# MySimpleRFMdongle_rev2.net
KiCad netlist of a schematic drawn in EAGLE
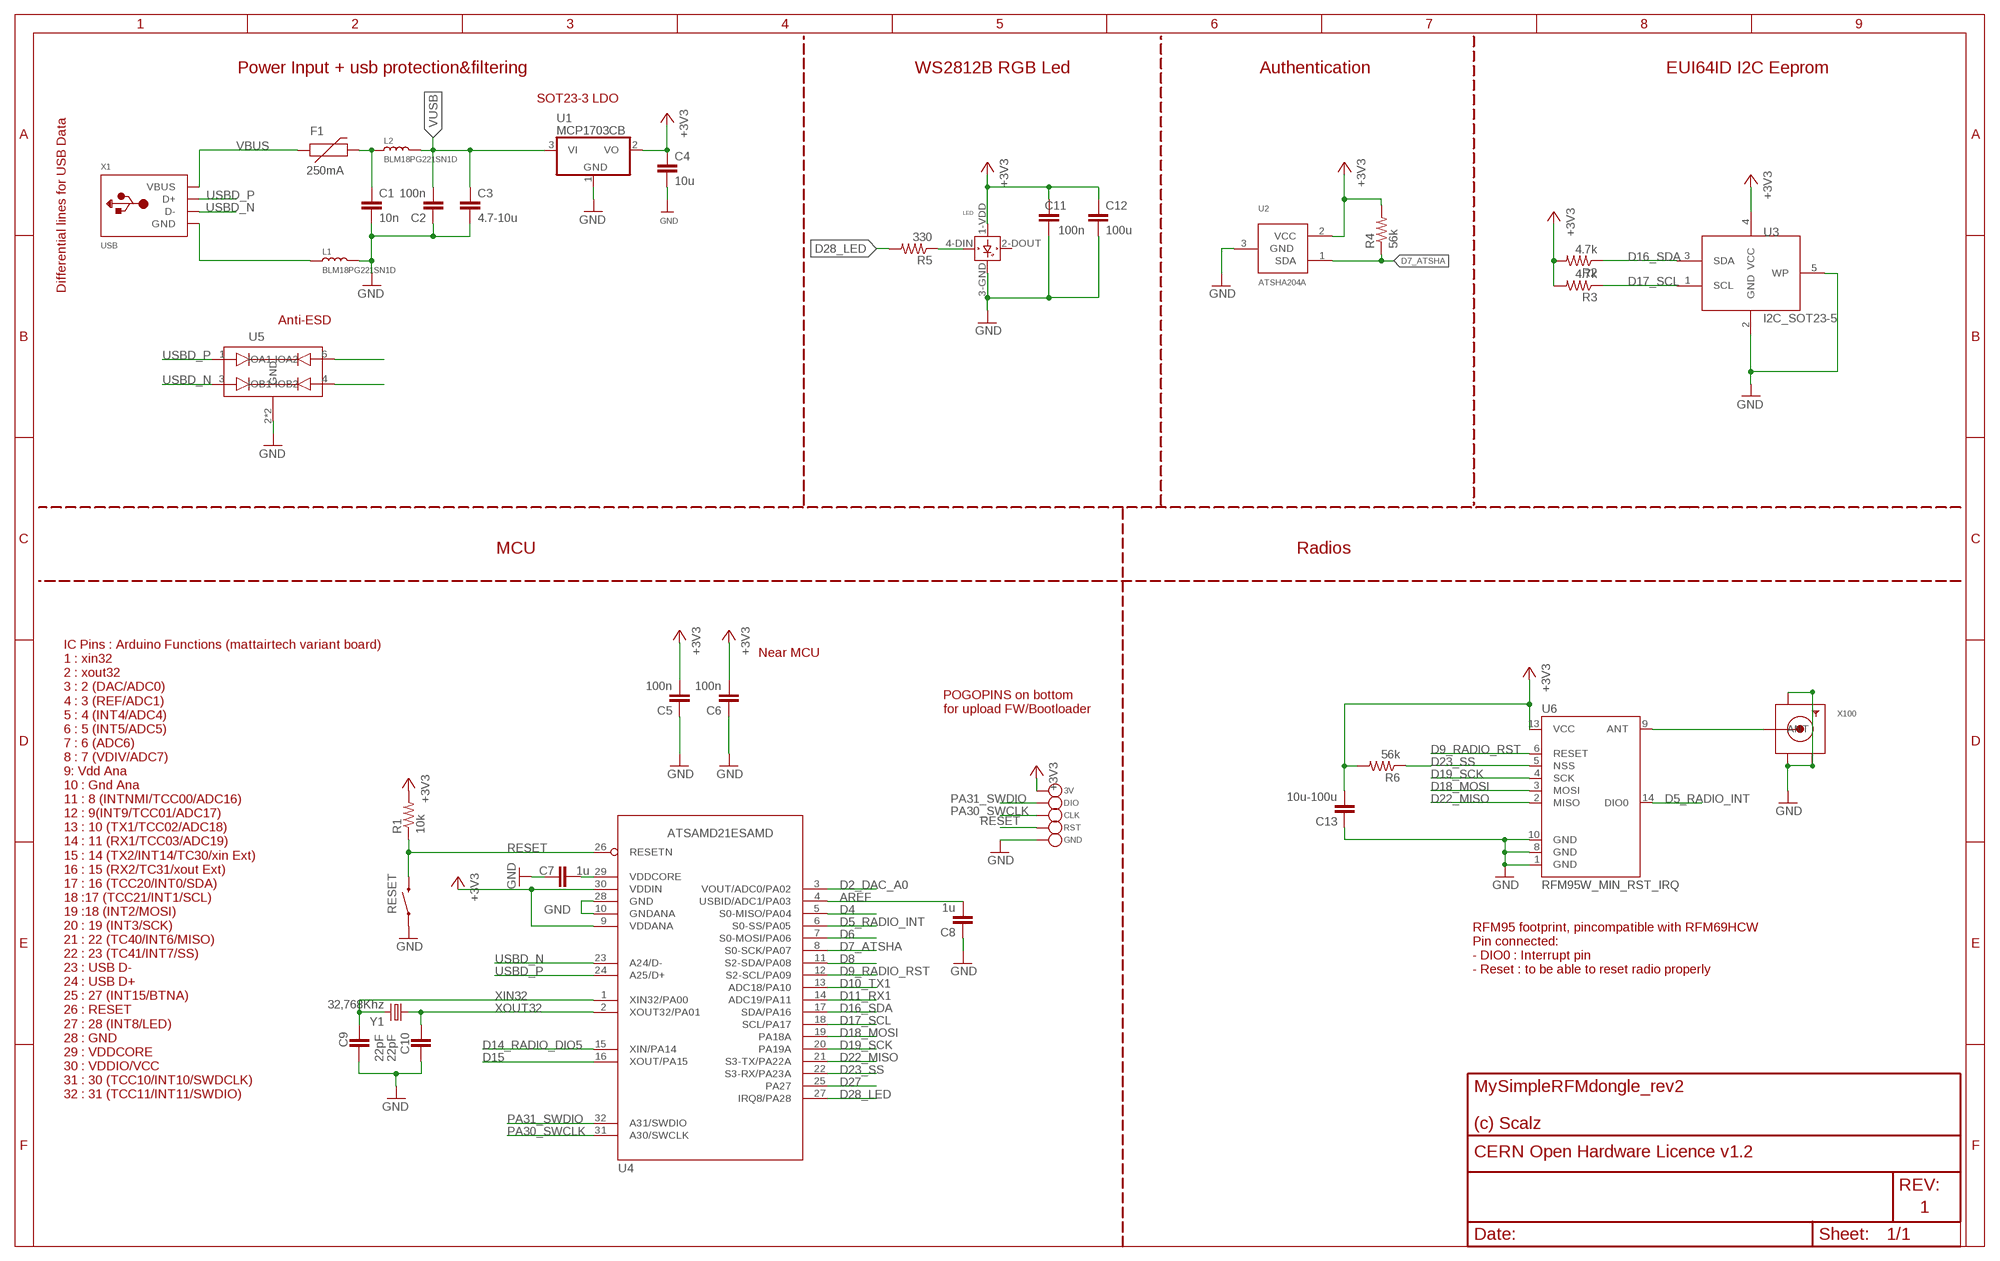
[diagram p0: schematic, sheet 1]

(export (version "E")
  (design (tool "Eeschema 10.0.6"))
  (components
    (comp (ref "3V")
      (value "TESTPOINTROUND1.5MM")
      (footprint "eagle-import:TESTPOINT_ROUND_1.5MM")
      (libsource (lib "eagle-import") (part "TESTPOINTROUND1.5MM"))
    )
    (comp (ref "C1")
      (value "10n")
      (footprint "eagle-import:0603-CAP")
      (libsource (lib "eagle-import") (part "CAP0603-CAP"))
    )
    (comp (ref "C2")
      (value "100n")
      (footprint "eagle-import:0603-CAP")
      (libsource (lib "eagle-import") (part "CAP0603-CAP"))
    )
    (comp (ref "C3")
      (value "4.7-10u")
      (footprint "eagle-import:0805-CAP")
      (libsource (lib "eagle-import") (part "CAP0805-CAP"))
    )
    (comp (ref "C4")
      (value "10u")
      (footprint "eagle-import:0805-CAP")
      (libsource (lib "eagle-import") (part "CAP0805-CAP"))
    )
    (comp (ref "C5")
      (value "100n")
      (footprint "eagle-import:0805-CAP")
      (libsource (lib "eagle-import") (part "CAP0805-CAP"))
    )
    (comp (ref "C6")
      (value "100n")
      (footprint "eagle-import:0603-CAP")
      (libsource (lib "eagle-import") (part "CAP0603-CAP"))
    )
    (comp (ref "C7")
      (value "1u")
      (footprint "eagle-import:0805-CAP")
      (libsource (lib "eagle-import") (part "CAP0805-CAP"))
    )
    (comp (ref "C8")
      (value "1u")
      (footprint "eagle-import:0603-CAP")
      (libsource (lib "eagle-import") (part "CAP0603-CAP"))
    )
    (comp (ref "C9")
      (value "22pF")
      (footprint "eagle-import:0603-CAP")
      (libsource (lib "eagle-import") (part "CAP0603-CAP"))
    )
    (comp (ref "C10")
      (value "22pF")
      (footprint "eagle-import:0603-CAP")
      (libsource (lib "eagle-import") (part "CAP0603-CAP"))
    )
    (comp (ref "C11")
      (value "100n")
      (footprint "eagle-import:0603-CAP")
      (libsource (lib "eagle-import") (part "CAP0603-CAP"))
    )
    (comp (ref "C12")
      (value "100u")
      (footprint "eagle-import:0805-CAP")
      (libsource (lib "eagle-import") (part "CAP0805-CAP"))
    )
    (comp (ref "C13")
      (value "10u-100u")
      (footprint "eagle-import:0805-CAP")
      (libsource (lib "eagle-import") (part "CAP0805-CAP"))
    )
    (comp (ref "CLK")
      (value "TESTPOINTROUND1.5MM")
      (footprint "eagle-import:TESTPOINT_ROUND_1.5MM")
      (libsource (lib "eagle-import") (part "TESTPOINTROUND1.5MM"))
    )
    (comp (ref "DIO")
      (value "TESTPOINTROUND1.5MM")
      (footprint "eagle-import:TESTPOINT_ROUND_1.5MM")
      (libsource (lib "eagle-import") (part "TESTPOINTROUND1.5MM"))
    )
    (comp (ref "F1")
      (value "250mA")
      (footprint "eagle-import:PTC-1206")
      (libsource (lib "eagle-import") (part "PTCSMD"))
    )
    (comp (ref "GND")
      (value "TESTPOINTROUND1.5MM")
      (footprint "eagle-import:TESTPOINT_ROUND_1.5MM")
      (libsource (lib "eagle-import") (part "TESTPOINTROUND1.5MM"))
    )
    (comp (ref "L1")
      (value "BLM18PG221SN1D")
      (footprint "eagle-import:L0603")
      (libsource (lib "eagle-import") (part "INDUCTOR/FERRITE-BEAD-0603"))
    )
    (comp (ref "L2")
      (value "BLM18PG221SN1D")
      (footprint "eagle-import:L0603")
      (libsource (lib "eagle-import") (part "INDUCTOR/FERRITE-BEAD-0603"))
    )
    (comp (ref "LED")
      (value "WS2812B")
      (footprint "eagle-import:WS2812B")
      (libsource (lib "eagle-import") (part "WS2812B"))
    )
    (comp (ref "R1")
      (value "10k")
      (footprint "eagle-import:0603-RES")
      (libsource (lib "eagle-import") (part "RESISTOR0603-RES"))
    )
    (comp (ref "R2")
      (value "4.7k")
      (footprint "eagle-import:0603-RES")
      (libsource (lib "eagle-import") (part "RESISTOR0603-RES"))
    )
    (comp (ref "R3")
      (value "4.7k")
      (footprint "eagle-import:0603-RES")
      (libsource (lib "eagle-import") (part "RESISTOR0603-RES"))
    )
    (comp (ref "R4")
      (value "56k")
      (footprint "eagle-import:0603-RES")
      (libsource (lib "eagle-import") (part "RESISTOR0603-RES"))
    )
    (comp (ref "R5")
      (value "330")
      (footprint "eagle-import:0603-RES")
      (libsource (lib "eagle-import") (part "RESISTOR0603-RES"))
    )
    (comp (ref "R6")
      (value "56k")
      (footprint "eagle-import:0603-RES")
      (libsource (lib "eagle-import") (part "RESISTOR0603-RES"))
    )
    (comp (ref "RESET")
      (value "SWITCH-MOMENTARY-2-SMD-1101NE")
      (footprint "eagle-import:TACTILE-SWITCH-1101NE")
      (libsource (lib "eagle-import") (part "SWITCH-MOMENTARY-2-SMD-1101NE"))
    )
    (comp (ref "RST")
      (value "TESTPOINTROUND1.5MM")
      (footprint "eagle-import:TESTPOINT_ROUND_1.5MM")
      (libsource (lib "eagle-import") (part "TESTPOINTROUND1.5MM"))
    )
    (comp (ref "U1")
      (value "MCP1703CB")
      (footprint "eagle-import:SOT23")
      (libsource (lib "eagle-import") (part "MCP1703CB"))
    )
    (comp (ref "U2")
      (value "ATSHA204A")
      (footprint "eagle-import:SOT23")
      (libsource (lib "eagle-import") (part "ATSHA204A"))
    )
    (comp (ref "U3")
      (value "I2C_SOT23-5")
      (footprint "eagle-import:SOT-23-5")
      (libsource (lib "eagle-import") (part "AT24CS32"))
    )
    (comp (ref "U4")
      (value "ATSAMD21ESAMD")
      (footprint "eagle-import:TQFP32-08")
      (libsource (lib "eagle-import") (part "ATSAMD21ESAMD"))
    )
    (comp (ref "U5")
      (value "TPD2E1B06")
      (footprint "eagle-import:TPD2E1B06")
      (libsource (lib "eagle-import") (part "TPD2E1B06"))
    )
    (comp (ref "U6")
      (value "RFM95W_MIN_RST_IRQ")
      (footprint "eagle-import:RFM95W_MINI_RST_IRQ")
      (libsource (lib "eagle-import") (part "RFM95W_MIN_RST_IRQ"))
    )
    (comp (ref "X1")
      (value "USB")
      (footprint "eagle-import:MOLEX-48037-1000")
      (libsource (lib "eagle-import") (part "USB"))
    )
    (comp (ref "X100")
      (value "SMACONNECTOR_EDGE")
      (footprint "eagle-import:SMA_EDGELAUNCH")
      (libsource (lib "eagle-import") (part "SMACONNECTOR_EDGE"))
    )
    (comp (ref "Y1")
      (value "32,768Khz")
      (footprint "eagle-import:CRYSTAL-SMD-2.0X1.2")
      (libsource (lib "eagle-import") (part "CRYSTAL2012"))
    )
  )
  (nets
    (net (code "1") (name "+3V3") (class "Default")
      (node (ref "3V") (pin "P$1") (pinfunction "P$1_P$1") (pintype "bidirectional"))
      (node (ref "C11") (pin "2") (pinfunction "2_2") (pintype "passive"))
      (node (ref "C12") (pin "1") (pinfunction "1_1") (pintype "passive"))
      (node (ref "C13") (pin "2") (pinfunction "2_2") (pintype "passive"))
      (node (ref "C4") (pin "1") (pinfunction "1_1") (pintype "passive"))
      (node (ref "C5") (pin "2") (pinfunction "2_2") (pintype "passive"))
      (node (ref "C6") (pin "2") (pinfunction "2_2") (pintype "passive"))
      (node (ref "LED") (pin "1-VDD") (pinfunction "VDD_1-VDD") (pintype "bidirectional"))
      (node (ref "R1") (pin "2") (pinfunction "2_2") (pintype "passive"))
      (node (ref "R2") (pin "2") (pinfunction "2_2") (pintype "passive"))
      (node (ref "R3") (pin "2") (pinfunction "2_2") (pintype "passive"))
      (node (ref "R4") (pin "2") (pinfunction "2_2") (pintype "passive"))
      (node (ref "R6") (pin "2") (pinfunction "2_2") (pintype "passive"))
      (node (ref "U1") (pin "2") (pinfunction "VO_2") (pintype "passive"))
      (node (ref "U2") (pin "2") (pinfunction "VCC_2") (pintype "bidirectional"))
      (node (ref "U3") (pin "4") (pinfunction "VCC_4") (pintype "bidirectional"))
      (node (ref "U4") (pin "30") (pinfunction "VDDIN_30") (pintype "bidirectional"))
      (node (ref "U4") (pin "9") (pinfunction "VDDANA_9") (pintype "bidirectional"))
      (node (ref "U6") (pin "13") (pinfunction "VCC_13") (pintype "bidirectional"))
    )
    (net (code "2") (name "/AREF") (class "Default")
      (node (ref "C8") (pin "2") (pinfunction "2_2") (pintype "passive"))
      (node (ref "U4") (pin "4") (pinfunction "USBID/ADC1/PA03_4") (pintype "bidirectional"))
    )
    (net (code "3") (name "/D2_DAC_A0") (class "Default")
      (node (ref "U4") (pin "3") (pinfunction "VOUT/ADC0/PA02_3") (pintype "bidirectional"))
    )
    (net (code "4") (name "/D4") (class "Default")
      (node (ref "U4") (pin "5") (pinfunction "S0-MISO/PA04_5") (pintype "bidirectional"))
    )
    (net (code "5") (name "/D5_RADIO_INT") (class "Default")
      (node (ref "U4") (pin "6") (pinfunction "S0-SS/PA05_6") (pintype "bidirectional"))
      (node (ref "U6") (pin "14") (pinfunction "DIO0_14") (pintype "input"))
    )
    (net (code "6") (name "/D6") (class "Default")
      (node (ref "U4") (pin "7") (pinfunction "S0-MOSI/PA06_7") (pintype "bidirectional"))
    )
    (net (code "7") (name "/D8") (class "Default")
      (node (ref "U4") (pin "11") (pinfunction "S2-SDA/PA08_11") (pintype "bidirectional"))
    )
    (net (code "8") (name "/D9_RADIO_RST") (class "Default")
      (node (ref "U4") (pin "12") (pinfunction "S2-SCL/PA09_12") (pintype "bidirectional"))
      (node (ref "U6") (pin "6") (pinfunction "RESET_6") (pintype "output"))
    )
    (net (code "9") (name "/D10_TX1") (class "Default")
      (node (ref "U4") (pin "13") (pinfunction "ADC18/PA10_13") (pintype "bidirectional"))
    )
    (net (code "10") (name "/D11_RX1") (class "Default")
      (node (ref "U4") (pin "14") (pinfunction "ADC19/PA11_14") (pintype "bidirectional"))
    )
    (net (code "11") (name "/D14_RADIO_DIO5") (class "Default")
      (node (ref "U4") (pin "15") (pinfunction "XIN/PA14_15") (pintype "bidirectional"))
    )
    (net (code "12") (name "/D15") (class "Default")
      (node (ref "U4") (pin "16") (pinfunction "XOUT/PA15_16") (pintype "bidirectional"))
    )
    (net (code "13") (name "/D16_SDA") (class "Default")
      (node (ref "R2") (pin "1") (pinfunction "1_1") (pintype "passive"))
      (node (ref "U3") (pin "3") (pinfunction "SDA_3") (pintype "bidirectional"))
      (node (ref "U4") (pin "17") (pinfunction "SDA/PA16_17") (pintype "bidirectional"))
    )
    (net (code "14") (name "/D17_SCL") (class "Default")
      (node (ref "R3") (pin "1") (pinfunction "1_1") (pintype "passive"))
      (node (ref "U3") (pin "1") (pinfunction "SCL_1") (pintype "bidirectional"))
      (node (ref "U4") (pin "18") (pinfunction "SCL/PA17_18") (pintype "bidirectional"))
    )
    (net (code "15") (name "/D18_MOSI") (class "Default")
      (node (ref "U4") (pin "19") (pinfunction "PA18A_19") (pintype "bidirectional"))
      (node (ref "U6") (pin "3") (pinfunction "MOSI_3") (pintype "input"))
    )
    (net (code "16") (name "/D19_SCK") (class "Default")
      (node (ref "U4") (pin "20") (pinfunction "PA19A_20") (pintype "bidirectional"))
      (node (ref "U6") (pin "4") (pinfunction "SCK_4") (pintype "input"))
    )
    (net (code "17") (name "/D22_MISO") (class "Default")
      (node (ref "U4") (pin "21") (pinfunction "S3-TX/PA22A_21") (pintype "bidirectional"))
      (node (ref "U6") (pin "2") (pinfunction "MISO_2") (pintype "output"))
    )
    (net (code "18") (name "/D23_SS") (class "Default")
      (node (ref "R6") (pin "1") (pinfunction "1_1") (pintype "passive"))
      (node (ref "U4") (pin "22") (pinfunction "S3-RX/PA23A_22") (pintype "bidirectional"))
      (node (ref "U6") (pin "5") (pinfunction "NSS_5") (pintype "input"))
    )
    (net (code "19") (name "/D27") (class "Default")
      (node (ref "U4") (pin "25") (pinfunction "PA27_25") (pintype "bidirectional"))
    )
    (net (code "20") (name "/PA30_SWCLK") (class "Default")
      (node (ref "CLK") (pin "P$1") (pinfunction "P$1_P$1") (pintype "bidirectional"))
      (node (ref "U4") (pin "31") (pinfunction "A30/SWCLK_31") (pintype "bidirectional"))
    )
    (net (code "21") (name "/PA31_SWDIO") (class "Default")
      (node (ref "DIO") (pin "P$1") (pinfunction "P$1_P$1") (pintype "bidirectional"))
      (node (ref "U4") (pin "32") (pinfunction "A31/SWDIO_32") (pintype "bidirectional"))
    )
    (net (code "22") (name "/RESET") (class "Default")
      (node (ref "R1") (pin "1") (pinfunction "1_1") (pintype "passive"))
      (node (ref "RESET") (pin "P$2") (pinfunction "2_P$2") (pintype "passive"))
      (node (ref "RST") (pin "P$1") (pinfunction "P$1_P$1") (pintype "bidirectional"))
      (node (ref "U4") (pin "26") (pinfunction "RESETN_26") (pintype "bidirectional"))
    )
    (net (code "23") (name "/USBD_N") (class "Default")
      (node (ref "U4") (pin "23") (pinfunction "A24/D-_23") (pintype "bidirectional"))
      (node (ref "U5") (pin "3") (pinfunction "IOB1_3") (pintype "bidirectional"))
      (node (ref "U5") (pin "4") (pinfunction "IOB2_4") (pintype "bidirectional"))
      (node (ref "X1") (pin "2") (pinfunction "D-_2") (pintype "bidirectional"))
    )
    (net (code "24") (name "/USBD_P") (class "Default")
      (node (ref "U4") (pin "24") (pinfunction "A25/D+_24") (pintype "bidirectional"))
      (node (ref "U5") (pin "1") (pinfunction "IOA1_1") (pintype "bidirectional"))
      (node (ref "U5") (pin "6") (pinfunction "IOA2_6") (pintype "bidirectional"))
      (node (ref "X1") (pin "3") (pinfunction "D+_3") (pintype "bidirectional"))
    )
    (net (code "25") (name "/VBUS") (class "Default")
      (node (ref "F1") (pin "1") (pinfunction "1_1") (pintype "bidirectional"))
      (node (ref "X1") (pin "1") (pinfunction "VBUS_1") (pintype "power_in"))
    )
    (net (code "26") (name "/XIN32") (class "Default")
      (node (ref "C9") (pin "2") (pinfunction "2_2") (pintype "passive"))
      (node (ref "U4") (pin "1") (pinfunction "XIN32/PA00_1") (pintype "bidirectional"))
      (node (ref "Y1") (pin "2") (pinfunction "2_2") (pintype "passive"))
    )
    (net (code "27") (name "/XOUT32") (class "Default")
      (node (ref "C10") (pin "2") (pinfunction "2_2") (pintype "passive"))
      (node (ref "U4") (pin "2") (pinfunction "XOUT32/PA01_2") (pintype "bidirectional"))
      (node (ref "Y1") (pin "1") (pinfunction "1_1") (pintype "passive"))
    )
    (net (code "28") (name "D7_ATSHA") (class "Default")
      (node (ref "R4") (pin "1") (pinfunction "1_1") (pintype "passive"))
      (node (ref "U2") (pin "1") (pinfunction "SDA_1") (pintype "bidirectional"))
      (node (ref "U4") (pin "8") (pinfunction "S0-SCK/PA07_8") (pintype "bidirectional"))
    )
    (net (code "29") (name "D28_LED") (class "Default")
      (node (ref "R5") (pin "2") (pinfunction "2_2") (pintype "passive"))
      (node (ref "U4") (pin "27") (pinfunction "IRQ8/PA28_27") (pintype "bidirectional"))
    )
    (net (code "30") (name "GND") (class "Default")
      (node (ref "C1") (pin "2") (pinfunction "2_2") (pintype "passive"))
      (node (ref "C10") (pin "1") (pinfunction "1_1") (pintype "passive"))
      (node (ref "C11") (pin "1") (pinfunction "1_1") (pintype "passive"))
      (node (ref "C12") (pin "2") (pinfunction "2_2") (pintype "passive"))
      (node (ref "C13") (pin "1") (pinfunction "1_1") (pintype "passive"))
      (node (ref "C2") (pin "1") (pinfunction "1_1") (pintype "passive"))
      (node (ref "C3") (pin "2") (pinfunction "2_2") (pintype "passive"))
      (node (ref "C4") (pin "2") (pinfunction "2_2") (pintype "passive"))
      (node (ref "C5") (pin "1") (pinfunction "1_1") (pintype "passive"))
      (node (ref "C6") (pin "1") (pinfunction "1_1") (pintype "passive"))
      (node (ref "C7") (pin "1") (pinfunction "1_1") (pintype "passive"))
      (node (ref "C8") (pin "1") (pinfunction "1_1") (pintype "passive"))
      (node (ref "C9") (pin "1") (pinfunction "1_1") (pintype "passive"))
      (node (ref "GND") (pin "P$1") (pinfunction "P$1_P$1") (pintype "bidirectional"))
      (node (ref "L1") (pin "2") (pinfunction "2_2") (pintype "passive"))
      (node (ref "LED") (pin "3-GND") (pinfunction "GND_3-GND") (pintype "bidirectional"))
      (node (ref "RESET") (pin "P$1") (pinfunction "1_P$1") (pintype "passive"))
      (node (ref "U1") (pin "1") (pinfunction "GND_1") (pintype "passive"))
      (node (ref "U2") (pin "3") (pinfunction "GND_3") (pintype "bidirectional"))
      (node (ref "U3") (pin "2") (pinfunction "GND_2") (pintype "bidirectional"))
      (node (ref "U3") (pin "5") (pinfunction "WP_5") (pintype "bidirectional"))
      (node (ref "U4") (pin "10") (pinfunction "GNDANA_10") (pintype "bidirectional"))
      (node (ref "U4") (pin "28") (pinfunction "GND_28") (pintype "bidirectional"))
      (node (ref "U5") (pin "2") (pinfunction "GND_2") (pintype "bidirectional"))
      (node (ref "U5") (pin "5") (pinfunction "GND_5") (pintype "bidirectional"))
      (node (ref "U6") (pin "1") (pinfunction "GND_1") (pintype "power_in"))
      (node (ref "U6") (pin "10") (pinfunction "GND_10") (pintype "power_in"))
      (node (ref "U6") (pin "8") (pinfunction "GND_8") (pintype "power_in"))
      (node (ref "X100") (pin "GND@1") (pinfunction "GND4_GND@1") (pintype "power_in"))
      (node (ref "X100") (pin "GND@2") (pinfunction "GND3_GND@2") (pintype "power_in"))
      (node (ref "X100") (pin "GND@3") (pinfunction "GND2_GND@3") (pintype "power_in"))
      (node (ref "X100") (pin "GND@4") (pinfunction "GND1_GND@4") (pintype "power_in"))
    )
    (net (code "31") (name "Net-(C1-Pad1)") (class "Default")
      (node (ref "C1") (pin "1") (pinfunction "1_1") (pintype "passive"))
      (node (ref "F1") (pin "2") (pinfunction "2_2") (pintype "bidirectional"))
      (node (ref "L2") (pin "1") (pinfunction "1_1") (pintype "passive"))
    )
    (net (code "32") (name "Net-(LED-DIN)") (class "Default")
      (node (ref "LED") (pin "4-DIN") (pinfunction "DIN_4-DIN") (pintype "input"))
      (node (ref "R5") (pin "1") (pinfunction "1_1") (pintype "passive"))
    )
    (net (code "33") (name "Net-(U4-VDDCORE)") (class "Default")
      (node (ref "C7") (pin "2") (pinfunction "2_2") (pintype "passive"))
      (node (ref "U4") (pin "29") (pinfunction "VDDCORE_29") (pintype "bidirectional"))
    )
    (net (code "34") (name "Net-(U6-ANT)") (class "Default")
      (node (ref "U6") (pin "9") (pinfunction "ANT_9") (pintype "bidirectional"))
      (node (ref "X100") (pin "P") (pinfunction "ANT_P") (pintype "bidirectional"))
    )
    (net (code "35") (name "Net-(X1-GND)") (class "Default")
      (node (ref "L1") (pin "1") (pinfunction "1_1") (pintype "passive"))
      (node (ref "X1") (pin "4") (pinfunction "GND_4") (pintype "power_in"))
    )
    (net (code "36") (name "VUSB") (class "Default")
      (node (ref "C2") (pin "2") (pinfunction "2_2") (pintype "passive"))
      (node (ref "C3") (pin "1") (pinfunction "1_1") (pintype "passive"))
      (node (ref "L2") (pin "2") (pinfunction "2_2") (pintype "passive"))
      (node (ref "U1") (pin "3") (pinfunction "VI_3") (pintype "input"))
    )
    (net (code "37") (name "unconnected-(LED-DOUT-Pad2-DOUT)") (class "Default")
      (node (ref "LED") (pin "2-DOUT") (pinfunction "DOUT_2-DOUT") (pintype "output"))
    )
  )
)
